# Sch4MainCardControl.net
KiCad netlist of a schematic drawn in Altium Designer
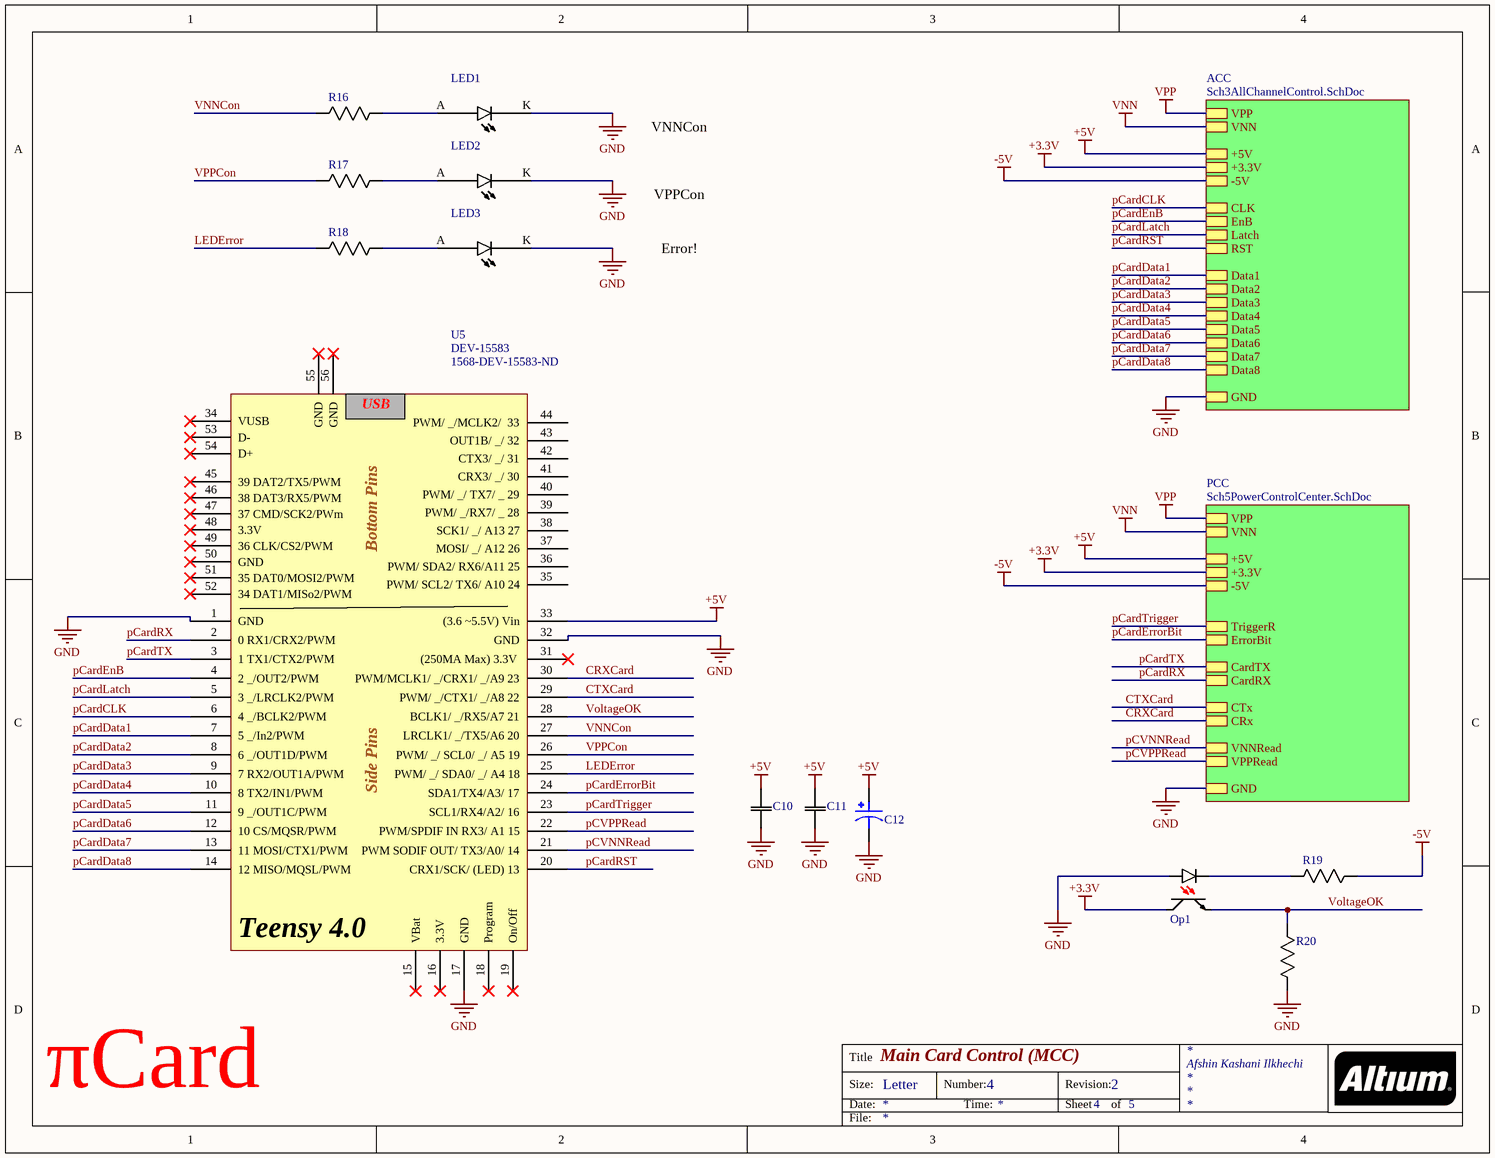
[diagram p0: Sch4MainCardControl.SchDoc]

(export (version "E")
  (design (tool "Eeschema 10.0.6"))
  (components
    (comp (ref "C10")
      (value "GRM155R71C103MA01D")
      (footprint "C0402")
      (libsource (lib "Afshin Library") (part "Cap_0402"))
    )
    (comp (ref "C11")
      (value "GRM155R71C103MA01D")
      (footprint "C0402")
      (libsource (lib "Afshin Library") (part "Cap_0402"))
    )
    (comp (ref "C12")
      (value "T55A107M6R3C0200")
      (footprint "C1206")
      (description "Tantalium")
      (libsource (lib "Afshin Library") (part "Cap_1206"))
    )
    (comp (ref "LED1")
      (value "LH R974-LP-1")
      (footprint "LEDr0805")
      (description "LED:\r\nLH R974-LP-1\r\nLG R971-KN-1\r\nLY R976-PS-36")
      (libsource (lib "Afshin Library") (part "LED_0805"))
    )
    (comp (ref "LED2")
      (value "LH R974-LP-1")
      (footprint "LEDr0805")
      (description "LED:\r\nLH R974-LP-1\r\nLG R971-KN-1\r\nLY R976-PS-36")
      (libsource (lib "Afshin Library") (part "LED_0805"))
    )
    (comp (ref "LED3")
      (value "LH R974-LP-1")
      (footprint "LEDr0805")
      (description "LED:\r\nLH R974-LP-1\r\nLG R971-KN-1\r\nLY R976-PS-36")
      (libsource (lib "Afshin Library") (part "LED_0805"))
    )
    (comp (ref "Op1")
      (value "TLP291(GB,SE")
      (footprint "4-SOIC")
      (libsource (lib "Afshin Library") (part "TLP291"))
    )
    (comp (ref "R16")
      (value "ERA-2AEB331X")
      (footprint "0402")
      (libsource (lib "Afshin Library") (part "Res_0805"))
    )
    (comp (ref "R17")
      (value "ERA-2AEB331X")
      (footprint "0402")
      (libsource (lib "Afshin Library") (part "Res_0805"))
    )
    (comp (ref "R18")
      (value "ERA-2AEB331X")
      (footprint "0402")
      (libsource (lib "Afshin Library") (part "Res_0805"))
    )
    (comp (ref "R19")
      (value "ERA-2AEB331X")
      (footprint "0402")
      (libsource (lib "Afshin Library") (part "Res_0805"))
    )
    (comp (ref "R20")
      (value "RK73B1ETTP103J")
      (footprint "R0402")
      (libsource (lib "Afshin Library") (part "Res_0402"))
    )
    (comp (ref "U5")
      (value "DEV-15583")
      (footprint "Teensy 4.0sideOnly")
      (fields (field (name "SUPPLIER PART NUMBER 1") "1568-DEV-15583-ND"))
      (libsource (lib "Afshin Library") (part "Teensy 4.0"))
    )
  )
  (nets
    (net (code "1") (name "+3.3V") (class "Default")
      (node (ref "Op1") (pin "4") (pinfunction "4_4") (pintype "passive"))
    )
    (net (code "2") (name "+5V") (class "Default")
      (node (ref "C10") (pin "2") (pinfunction "2_2") (pintype "passive"))
      (node (ref "C11") (pin "2") (pinfunction "2_2") (pintype "passive"))
      (node (ref "C12") (pin "1") (pinfunction "POS_1") (pintype "passive"))
      (node (ref "U5") (pin "33") (pinfunction "(3.6_~5.5V)_Vin_33") (pintype "passive"))
    )
    (net (code "3") (name "-5V") (class "Default")
      (node (ref "R19") (pin "1") (pinfunction "1_1") (pintype "passive"))
    )
    (net (code "4") (name "/CRXCard") (class "Default")
      (node (ref "U5") (pin "30") (pinfunction "PWM/MCLK1/__/CRX1/__/A9_23_30") (pintype "passive"))
    )
    (net (code "5") (name "/CTXCard") (class "Default")
      (node (ref "U5") (pin "29") (pinfunction "PWM/__/CTX1/__/A8_22_29") (pintype "passive"))
    )
    (net (code "6") (name "/LEDError") (class "Default")
      (node (ref "R18") (pin "2") (pinfunction "2_2") (pintype "passive"))
      (node (ref "U5") (pin "25") (pinfunction "PWM/__/_SDA0/__/_A4_18_25") (pintype "passive"))
    )
    (net (code "7") (name "/VNNCon") (class "Default")
      (node (ref "R16") (pin "2") (pinfunction "2_2") (pintype "passive"))
      (node (ref "U5") (pin "27") (pinfunction "LRCLK1/__/TX5/A6_20_27") (pintype "passive"))
    )
    (net (code "8") (name "/VPPCon") (class "Default")
      (node (ref "R17") (pin "2") (pinfunction "2_2") (pintype "passive"))
      (node (ref "U5") (pin "26") (pinfunction "PWM/__/_SCL0/__/_A5_19_26") (pintype "passive"))
    )
    (net (code "9") (name "/VoltageOK") (class "Default")
      (node (ref "Op1") (pin "3") (pinfunction "3_3") (pintype "passive"))
      (node (ref "R20") (pin "2") (pinfunction "2_2") (pintype "passive"))
      (node (ref "U5") (pin "28") (pinfunction "BCLK1/__/RX5/A7_21_28") (pintype "passive"))
    )
    (net (code "10") (name "/pCVNNRead") (class "Default")
      (node (ref "U5") (pin "21") (pinfunction "PWM_SODIF_OUT/_TX3/A0/_14_21") (pintype "passive"))
    )
    (net (code "11") (name "/pCVPPRead") (class "Default")
      (node (ref "U5") (pin "22") (pinfunction "PWM/SPDIF_IN_RX3/_A1_15_22") (pintype "passive"))
    )
    (net (code "12") (name "/pCardCLK") (class "Default")
      (node (ref "U5") (pin "6") (pinfunction "4__/BCLK2/PWM_6") (pintype "passive"))
    )
    (net (code "13") (name "/pCardData1") (class "Default")
      (node (ref "U5") (pin "7") (pinfunction "5__/In2/PWM_7") (pintype "passive"))
    )
    (net (code "14") (name "/pCardData2") (class "Default")
      (node (ref "U5") (pin "8") (pinfunction "6__/OUT1D/PWM_8") (pintype "passive"))
    )
    (net (code "15") (name "/pCardData3") (class "Default")
      (node (ref "U5") (pin "9") (pinfunction "7_RX2/OUT1A/PWM_9") (pintype "passive"))
    )
    (net (code "16") (name "/pCardData4") (class "Default")
      (node (ref "U5") (pin "10") (pinfunction "8_TX2/IN1/PWM_10") (pintype "passive"))
    )
    (net (code "17") (name "/pCardData5") (class "Default")
      (node (ref "U5") (pin "11") (pinfunction "9__/OUT1C/PWM_11") (pintype "passive"))
    )
    (net (code "18") (name "/pCardData6") (class "Default")
      (node (ref "U5") (pin "12") (pinfunction "10_CS/MQSR/PWM_12") (pintype "passive"))
    )
    (net (code "19") (name "/pCardData7") (class "Default")
      (node (ref "U5") (pin "13") (pinfunction "11_MOSI/CTX1/PWM_13") (pintype "passive"))
    )
    (net (code "20") (name "/pCardData8") (class "Default")
      (node (ref "U5") (pin "14") (pinfunction "12_MISO/MQSL/PWM_14") (pintype "passive"))
    )
    (net (code "21") (name "/pCardEnB") (class "Default")
      (node (ref "U5") (pin "4") (pinfunction "2__/OUT2/PWM_4") (pintype "passive"))
    )
    (net (code "22") (name "/pCardErrorBit") (class "Default")
      (node (ref "U5") (pin "24") (pinfunction "SDA1/TX4/A3/_17_24") (pintype "passive"))
    )
    (net (code "23") (name "/pCardLatch") (class "Default")
      (node (ref "U5") (pin "5") (pinfunction "3__/LRCLK2/PWM_5") (pintype "passive"))
    )
    (net (code "24") (name "/pCardRST") (class "Default")
      (node (ref "U5") (pin "20") (pinfunction "CRX1/SCK/_(LED)_13_20") (pintype "passive"))
    )
    (net (code "25") (name "/pCardRX") (class "Default")
      (node (ref "U5") (pin "2") (pinfunction "0_RX1/CRX2/PWM_2") (pintype "passive"))
    )
    (net (code "26") (name "/pCardTX") (class "Default")
      (node (ref "U5") (pin "3") (pinfunction "1_TX1/CTX2/PWM_3") (pintype "passive"))
    )
    (net (code "27") (name "/pCardTrigger") (class "Default")
      (node (ref "U5") (pin "23") (pinfunction "SCL1/RX4/A2/_16_23") (pintype "passive"))
    )
    (net (code "28") (name "GND") (class "Default")
      (node (ref "C10") (pin "1") (pinfunction "1_1") (pintype "passive"))
      (node (ref "C11") (pin "1") (pinfunction "1_1") (pintype "passive"))
      (node (ref "C12") (pin "2") (pinfunction "NEG_2") (pintype "passive"))
      (node (ref "LED1") (pin "K") (pinfunction "k_K") (pintype "passive"))
      (node (ref "LED2") (pin "K") (pinfunction "k_K") (pintype "passive"))
      (node (ref "LED3") (pin "K") (pinfunction "k_K") (pintype "passive"))
      (node (ref "Op1") (pin "1") (pinfunction "1_1") (pintype "passive"))
      (node (ref "R20") (pin "1") (pinfunction "1_1") (pintype "passive"))
      (node (ref "U5") (pin "1") (pinfunction "GND_1") (pintype "passive"))
      (node (ref "U5") (pin "17") (pinfunction "GND_17") (pintype "passive"))
      (node (ref "U5") (pin "32") (pinfunction "GND_32") (pintype "passive"))
    )
    (net (code "29") (name "Net-(LED1-PadA)") (class "Default")
      (node (ref "LED1") (pin "A") (pinfunction "A_A") (pintype "passive"))
      (node (ref "R16") (pin "1") (pinfunction "1_1") (pintype "passive"))
    )
    (net (code "30") (name "Net-(LED2-PadA)") (class "Default")
      (node (ref "LED2") (pin "A") (pinfunction "A_A") (pintype "passive"))
      (node (ref "R17") (pin "1") (pinfunction "1_1") (pintype "passive"))
    )
    (net (code "31") (name "Net-(LED3-PadA)") (class "Default")
      (node (ref "LED3") (pin "A") (pinfunction "A_A") (pintype "passive"))
      (node (ref "R18") (pin "1") (pinfunction "1_1") (pintype "passive"))
    )
    (net (code "32") (name "Net-(Op1-Pad2)") (class "Default")
      (node (ref "Op1") (pin "2") (pinfunction "2_2") (pintype "passive"))
      (node (ref "R19") (pin "2") (pinfunction "2_2") (pintype "passive"))
    )
    (net (code "35") (name "unconnected-(U5-(250MA_Max)_3.3V-Pad31)") (class "Default")
      (node (ref "U5") (pin "31") (pinfunction "(250MA_Max)_3.3V_31") (pintype "passive+no_connect"))
    )
    (net (code "36") (name "unconnected-(U5-3.3V-Pad16)") (class "Default")
      (node (ref "U5") (pin "16") (pinfunction "3.3V_16") (pintype "passive+no_connect"))
    )
    (net (code "37") (name "unconnected-(U5-3.3V-Pad48)") (class "Default")
      (node (ref "U5") (pin "48") (pinfunction "3.3V_48") (pintype "passive+no_connect"))
    )
    (net (code "38") (name "unconnected-(U5-34_DAT1{slash}MISo2{slash}PWM-Pad52)") (class "Default")
      (node (ref "U5") (pin "52") (pinfunction "34_DAT1/MISo2/PWM_52") (pintype "passive+no_connect"))
    )
    (net (code "39") (name "unconnected-(U5-35_DAT0{slash}MOSI2{slash}PWM-Pad51)") (class "Default")
      (node (ref "U5") (pin "51") (pinfunction "35_DAT0/MOSI2/PWM_51") (pintype "passive+no_connect"))
    )
    (net (code "40") (name "unconnected-(U5-36_CLK{slash}CS2{slash}PWM-Pad49)") (class "Default")
      (node (ref "U5") (pin "49") (pinfunction "36_CLK/CS2/PWM_49") (pintype "passive+no_connect"))
    )
    (net (code "41") (name "unconnected-(U5-37_CMD{slash}SCK2{slash}PWm-Pad47)") (class "Default")
      (node (ref "U5") (pin "47") (pinfunction "37_CMD/SCK2/PWm_47") (pintype "passive+no_connect"))
    )
    (net (code "42") (name "unconnected-(U5-38_DAT3{slash}RX5{slash}PWM-Pad46)") (class "Default")
      (node (ref "U5") (pin "46") (pinfunction "38_DAT3/RX5/PWM_46") (pintype "passive+no_connect"))
    )
    (net (code "43") (name "unconnected-(U5-39_DAT2{slash}TX5{slash}PWM-Pad45)") (class "Default")
      (node (ref "U5") (pin "45") (pinfunction "39_DAT2/TX5/PWM_45") (pintype "passive+no_connect"))
    )
    (net (code "44") (name "unconnected-(U5-CRX3{slash}__{slash}_30-Pad41)") (class "Default")
      (node (ref "U5") (pin "41") (pinfunction "CRX3/__/_30_41") (pintype "passive"))
    )
    (net (code "45") (name "unconnected-(U5-CTX3{slash}__{slash}_31-Pad42)") (class "Default")
      (node (ref "U5") (pin "42") (pinfunction "CTX3/__/_31_42") (pintype "passive"))
    )
    (net (code "46") (name "unconnected-(U5-D+-Pad54)") (class "Default")
      (node (ref "U5") (pin "54") (pinfunction "D+_54") (pintype "passive+no_connect"))
    )
    (net (code "47") (name "unconnected-(U5-D--Pad53)") (class "Default")
      (node (ref "U5") (pin "53") (pinfunction "D-_53") (pintype "passive+no_connect"))
    )
    (net (code "48") (name "unconnected-(U5-GND-Pad50)") (class "Default")
      (node (ref "U5") (pin "50") (pinfunction "GND_50") (pintype "passive+no_connect"))
    )
    (net (code "49") (name "unconnected-(U5-GND-Pad55)") (class "Default")
      (node (ref "U5") (pin "55") (pinfunction "GND_55") (pintype "passive+no_connect"))
    )
    (net (code "50") (name "unconnected-(U5-GND-Pad56)") (class "Default")
      (node (ref "U5") (pin "56") (pinfunction "GND_56") (pintype "passive+no_connect"))
    )
    (net (code "51") (name "unconnected-(U5-MOSI{slash}__{slash}_A12_26-Pad37)") (class "Default")
      (node (ref "U5") (pin "37") (pinfunction "MOSI/__/_A12_26_37") (pintype "passive"))
    )
    (net (code "52") (name "unconnected-(U5-OUT1B{slash}__{slash}_32-Pad43)") (class "Default")
      (node (ref "U5") (pin "43") (pinfunction "OUT1B/__/_32_43") (pintype "passive"))
    )
    (net (code "53") (name "unconnected-(U5-On{slash}Off-Pad19)") (class "Default")
      (node (ref "U5") (pin "19") (pinfunction "On/Off_19") (pintype "passive+no_connect"))
    )
    (net (code "54") (name "unconnected-(U5-PWM{slash}_SCL2{slash}_TX6{slash}_A10_24-Pad35)") (class "Default")
      (node (ref "U5") (pin "35") (pinfunction "PWM/_SCL2/_TX6/_A10_24_35") (pintype "passive"))
    )
    (net (code "55") (name "unconnected-(U5-PWM{slash}_SDA2{slash}_RX6{slash}A11_25-Pad36)") (class "Default")
      (node (ref "U5") (pin "36") (pinfunction "PWM/_SDA2/_RX6/A11_25_36") (pintype "passive"))
    )
    (net (code "56") (name "unconnected-(U5-PWM{slash}__{slash}MCLK2{slash}__33-Pad44)") (class "Default")
      (node (ref "U5") (pin "44") (pinfunction "PWM/__/MCLK2/__33_44") (pintype "passive"))
    )
    (net (code "57") (name "unconnected-(U5-PWM{slash}__{slash}RX7{slash}___28-Pad39)") (class "Default")
      (node (ref "U5") (pin "39") (pinfunction "PWM/__/RX7/___28_39") (pintype "passive"))
    )
    (net (code "58") (name "unconnected-(U5-PWM{slash}__{slash}_TX7{slash}___29-Pad40)") (class "Default")
      (node (ref "U5") (pin "40") (pinfunction "PWM/__/_TX7/___29_40") (pintype "passive"))
    )
    (net (code "59") (name "unconnected-(U5-Program-Pad18)") (class "Default")
      (node (ref "U5") (pin "18") (pinfunction "Program_18") (pintype "passive+no_connect"))
    )
    (net (code "60") (name "unconnected-(U5-SCK1{slash}__{slash}_A13_27-Pad38)") (class "Default")
      (node (ref "U5") (pin "38") (pinfunction "SCK1/__/_A13_27_38") (pintype "passive"))
    )
    (net (code "61") (name "unconnected-(U5-VBat-Pad15)") (class "Default")
      (node (ref "U5") (pin "15") (pinfunction "VBat_15") (pintype "passive+no_connect"))
    )
    (net (code "62") (name "unconnected-(U5-VUSB-Pad34)") (class "Default")
      (node (ref "U5") (pin "34") (pinfunction "VUSB_34") (pintype "passive+no_connect"))
    )
  )
)
